# Labrador.net
KiCad netlist of a schematic drawn in Altium Designer
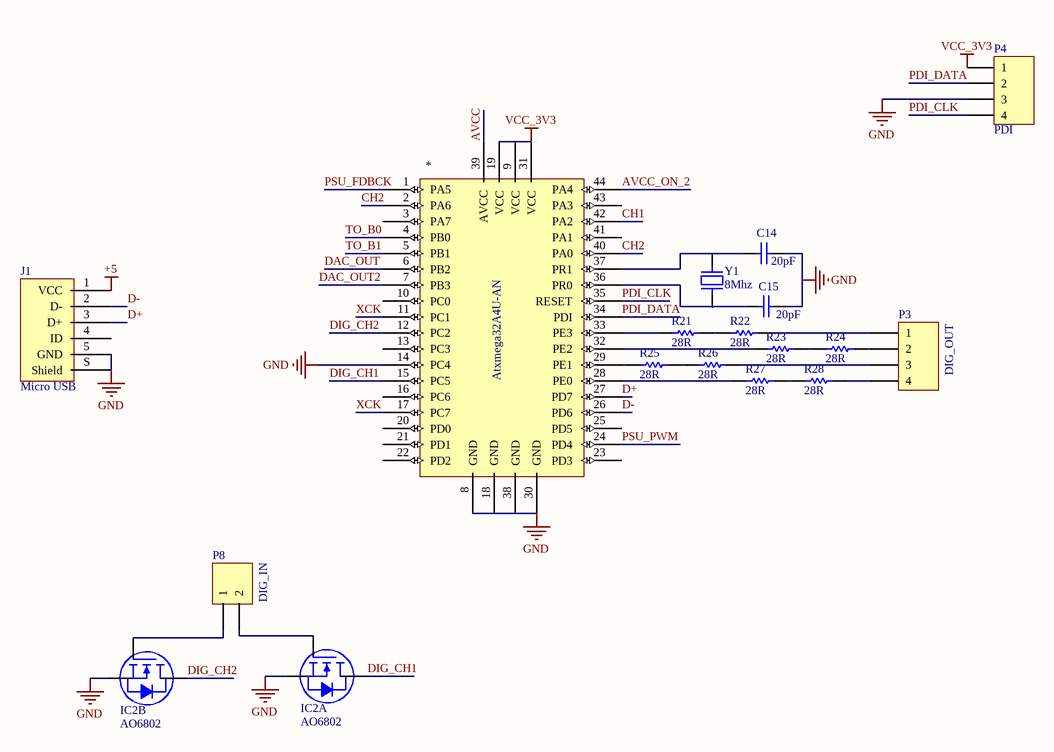
[diagram p0: Labrador.SchDoc]

(export (version "E")
  (design (tool "Eeschema 10.0.6"))
  (components
    (comp (ref "*")
      (value "Atxmega32A4U-AN")
      (footprint "QFP44P80_1200X1200X120L60X37N")
      (libsource (lib "labrador") (part "Atxmega32A4U-AN"))
    )
    (comp (ref "C14")
      (value "20pF")
      (footprint "CAPC200X125X75L45N")
      (description "CAP CER 20PF 50V NP0 0805")
      (fields
        (field (name "MANUFACTURER") "Samsung Electro-Mechanics America, Inc.")
        (field (name "MANUFACTURER PART NUMBER") "CL21C180JBANNNC")
      )
      (libsource (lib "labrador") (part "CL21C180JBANNNC"))
    )
    (comp (ref "C15")
      (value "20pF")
      (footprint "CAPC200X125X75L45N")
      (description "CAP CER 20PF 50V NP0 0805")
      (fields
        (field (name "MANUFACTURER") "Samsung Electro-Mechanics America, Inc.")
        (field (name "MANUFACTURER PART NUMBER") "CL21C180JBANNNC")
      )
      (libsource (lib "labrador") (part "CL21C180JBANNNC"))
    )
    (comp (ref "IC2")
      (value "AO6802")
      (footprint "ALPHAOMEGA TSOP-6")
      (description "MOSFET 2N-CH 30V 3.5A 6-TSOP")
      (fields (field (name "MANUFACTURER") "Alpha & Omega"))
      (libsource (lib "labrador") (part "ALPHAOMEGA TSOP-6"))
    )
    (comp (ref "J1")
      (value "Micro USB")
      (footprint "FCI USB 10118193-0001LF")
      (description "CONN USB MICRO B RECPT SMT R/A")
      (fields (field (name "PART NUMBER") "10118193-0001LF") (field (name "MANUFACTURER") "FCI"))
      (libsource (lib "labrador") (part "USB 2.0 Type B Micro"))
    )
    (comp (ref "P3")
      (value "DIG_OUT")
      (footprint "HDR1X4")
      (description "Header, 4-Pin")
      (fields (field (name "PUBLISHER") "Altium Limited"))
      (libsource (lib "labrador") (part "Header 4"))
    )
    (comp (ref "P4")
      (value "PDI")
      (footprint "HDR1X4")
      (description "Header, 4-Pin")
      (fields (field (name "PUBLISHER") "Altium Limited"))
      (libsource (lib "labrador") (part "Header 4"))
    )
    (comp (ref "P8")
      (value "DIG_IN")
      (footprint "HDR1X2")
      (description "Header, 2-Pin")
      (fields (field (name "PUBLISHER") "Altium Limited"))
      (libsource (lib "labrador") (part "Header 2"))
    )
    (comp (ref "R21")
      (value "28R")
      (footprint "RESC160X80X55L25N")
      (description "RES SMD 28 OHM 1% 1/10W 0603")
      (fields
        (field (name "MANUFACTURER") "Yageo")
        (field (name "MANUFACTURER PART NUMBER") "RC0603FR-0728RL")
      )
      (libsource (lib "labrador") (part "RC0603FR-0728RL"))
    )
    (comp (ref "R22")
      (value "28R")
      (footprint "RESC160X80X55L25N")
      (description "RES SMD 28 OHM 1% 1/10W 0603")
      (fields
        (field (name "MANUFACTURER") "Yageo")
        (field (name "MANUFACTURER PART NUMBER") "RC0603FR-0728RL")
      )
      (libsource (lib "labrador") (part "RC0603FR-0728RL"))
    )
    (comp (ref "R23")
      (value "28R")
      (footprint "RESC160X80X55L25N")
      (description "RES SMD 28 OHM 1% 1/10W 0603")
      (fields
        (field (name "MANUFACTURER") "Yageo")
        (field (name "MANUFACTURER PART NUMBER") "RC0603FR-0728RL")
      )
      (libsource (lib "labrador") (part "RC0603FR-0728RL"))
    )
    (comp (ref "R24")
      (value "28R")
      (footprint "RESC160X80X55L25N")
      (description "RES SMD 28 OHM 1% 1/10W 0603")
      (fields
        (field (name "MANUFACTURER") "Yageo")
        (field (name "MANUFACTURER PART NUMBER") "RC0603FR-0728RL")
      )
      (libsource (lib "labrador") (part "RC0603FR-0728RL"))
    )
    (comp (ref "R25")
      (value "28R")
      (footprint "RESC160X80X55L25N")
      (description "RES SMD 28 OHM 1% 1/10W 0603")
      (fields
        (field (name "MANUFACTURER") "Yageo")
        (field (name "MANUFACTURER PART NUMBER") "RC0603FR-0728RL")
      )
      (libsource (lib "labrador") (part "RC0603FR-0728RL"))
    )
    (comp (ref "R26")
      (value "28R")
      (footprint "RESC160X80X55L25N")
      (description "RES SMD 28 OHM 1% 1/10W 0603")
      (fields
        (field (name "MANUFACTURER") "Yageo")
        (field (name "MANUFACTURER PART NUMBER") "RC0603FR-0728RL")
      )
      (libsource (lib "labrador") (part "RC0603FR-0728RL"))
    )
    (comp (ref "R27")
      (value "28R")
      (footprint "RESC160X80X55L25N")
      (description "RES SMD 28 OHM 1% 1/10W 0603")
      (fields
        (field (name "MANUFACTURER") "Yageo")
        (field (name "MANUFACTURER PART NUMBER") "RC0603FR-0728RL")
      )
      (libsource (lib "labrador") (part "RC0603FR-0728RL"))
    )
    (comp (ref "R28")
      (value "28R")
      (footprint "RESC160X80X55L25N")
      (description "RES SMD 28 OHM 1% 1/10W 0603")
      (fields
        (field (name "MANUFACTURER") "Yageo")
        (field (name "MANUFACTURER PART NUMBER") "RC0603FR-0728RL")
      )
      (libsource (lib "labrador") (part "RC0603FR-0728RL"))
    )
    (comp (ref "Y1")
      (value "8Mhz")
      (footprint "TXC 9C")
      (description "Crystals 8MHz 20pF")
      (fields (field (name "MANUFACTURER") "CTS") (field (name "MANUFACTURER PART NUMBER") "ATS08ASM-1"))
      (libsource (lib "labrador") (part "ATS08ASM-1"))
    )
  )
  (nets
    (net (code "1") (name "+5") (class "Default")
      (node (ref "J1") (pin "1") (pinfunction "VCC_1") (pintype "passive"))
    )
    (net (code "2") (name "/AVCC") (class "Default")
      (node (ref "*") (pin "39") (pinfunction "AVCC_39") (pintype "power_in"))
    )
    (net (code "3") (name "/AVCC_ON_2") (class "Default")
      (node (ref "*") (pin "44") (pinfunction "PA4_44") (pintype "bidirectional"))
    )
    (net (code "4") (name "/CH1") (class "Default")
      (node (ref "*") (pin "42") (pinfunction "PA2_42") (pintype "bidirectional"))
    )
    (net (code "5") (name "/CH2") (class "Default")
      (node (ref "*") (pin "2") (pinfunction "PA6_2") (pintype "bidirectional"))
      (node (ref "*") (pin "40") (pinfunction "PA0_40") (pintype "bidirectional"))
    )
    (net (code "6") (name "/D+") (class "Default")
      (node (ref "*") (pin "27") (pinfunction "PD7_27") (pintype "bidirectional"))
      (node (ref "J1") (pin "3") (pinfunction "D+_3") (pintype "passive"))
    )
    (net (code "7") (name "/D-") (class "Default")
      (node (ref "*") (pin "26") (pinfunction "PD6_26") (pintype "bidirectional"))
      (node (ref "J1") (pin "2") (pinfunction "D-_2") (pintype "passive"))
    )
    (net (code "8") (name "/DAC_OUT") (class "Default")
      (node (ref "*") (pin "6") (pinfunction "PB2_6") (pintype "bidirectional"))
    )
    (net (code "9") (name "/DAC_OUT2") (class "Default")
      (node (ref "*") (pin "7") (pinfunction "PB3_7") (pintype "bidirectional"))
    )
    (net (code "10") (name "/DIG_CH1") (class "Default")
      (node (ref "*") (pin "15") (pinfunction "PC5_15") (pintype "bidirectional"))
      (node (ref "IC2") (pin "6") (pinfunction "D1_6") (pintype "passive"))
    )
    (net (code "11") (name "/DIG_CH2") (class "Default")
      (node (ref "*") (pin "12") (pinfunction "PC2_12") (pintype "bidirectional"))
      (node (ref "IC2") (pin "4") (pinfunction "D2_4") (pintype "passive"))
    )
    (net (code "12") (name "/PDI_CLK") (class "Default")
      (node (ref "*") (pin "35") (pinfunction "RESET_35") (pintype "bidirectional"))
      (node (ref "P4") (pin "4") (pinfunction "4_4") (pintype "passive"))
    )
    (net (code "13") (name "/PDI_DATA") (class "Default")
      (node (ref "*") (pin "34") (pinfunction "PDI_34") (pintype "bidirectional"))
      (node (ref "P4") (pin "2") (pinfunction "2_2") (pintype "passive"))
    )
    (net (code "14") (name "/PSU_FDBCK") (class "Default")
      (node (ref "*") (pin "1") (pinfunction "PA5_1") (pintype "bidirectional"))
    )
    (net (code "15") (name "/PSU_PWM") (class "Default")
      (node (ref "*") (pin "24") (pinfunction "PD4_24") (pintype "bidirectional"))
    )
    (net (code "16") (name "/TO_B0") (class "Default")
      (node (ref "*") (pin "4") (pinfunction "PB0_4") (pintype "bidirectional"))
    )
    (net (code "17") (name "/TO_B1") (class "Default")
      (node (ref "*") (pin "5") (pinfunction "PB1_5") (pintype "bidirectional"))
    )
    (net (code "18") (name "/XCK") (class "Default")
      (node (ref "*") (pin "11") (pinfunction "PC1_11") (pintype "bidirectional"))
      (node (ref "*") (pin "17") (pinfunction "PC7_17") (pintype "bidirectional"))
    )
    (net (code "19") (name "GND") (class "Default")
      (node (ref "*") (pin "14") (pinfunction "PC4_14") (pintype "bidirectional"))
      (node (ref "*") (pin "18") (pinfunction "GND_18") (pintype "power_in"))
      (node (ref "*") (pin "30") (pinfunction "GND_30") (pintype "power_in"))
      (node (ref "*") (pin "38") (pinfunction "GND_38") (pintype "power_in"))
      (node (ref "*") (pin "8") (pinfunction "GND_8") (pintype "power_in"))
      (node (ref "C14") (pin "2") (pinfunction "2_2") (pintype "passive"))
      (node (ref "C15") (pin "2") (pinfunction "2_2") (pintype "passive"))
      (node (ref "IC2") (pin "2") (pinfunction "S2_2") (pintype "passive"))
      (node (ref "IC2") (pin "5") (pinfunction "S1_5") (pintype "passive"))
      (node (ref "J1") (pin "5") (pinfunction "GND_5") (pintype "passive"))
      (node (ref "J1") (pin "S") (pinfunction "Shield_S") (pintype "passive"))
      (node (ref "P4") (pin "3") (pinfunction "3_3") (pintype "passive"))
    )
    (net (code "20") (name "Net-(*-PE0)") (class "Default")
      (node (ref "*") (pin "28") (pinfunction "PE0_28") (pintype "bidirectional"))
      (node (ref "R27") (pin "1") (pinfunction "1_1") (pintype "passive"))
    )
    (net (code "21") (name "Net-(*-PE1)") (class "Default")
      (node (ref "*") (pin "29") (pinfunction "PE1_29") (pintype "bidirectional"))
      (node (ref "R25") (pin "1") (pinfunction "1_1") (pintype "passive"))
    )
    (net (code "22") (name "Net-(*-PE2)") (class "Default")
      (node (ref "*") (pin "32") (pinfunction "PE2_32") (pintype "bidirectional"))
      (node (ref "R23") (pin "1") (pinfunction "1_1") (pintype "passive"))
    )
    (net (code "23") (name "Net-(*-PE3)") (class "Default")
      (node (ref "*") (pin "33") (pinfunction "PE3_33") (pintype "bidirectional"))
      (node (ref "R21") (pin "1") (pinfunction "1_1") (pintype "passive"))
    )
    (net (code "24") (name "Net-(*-PR0)") (class "Default")
      (node (ref "*") (pin "36") (pinfunction "PR0_36") (pintype "bidirectional"))
      (node (ref "C15") (pin "1") (pinfunction "1_1") (pintype "passive"))
      (node (ref "Y1") (pin "1") (pinfunction "1_1") (pintype "passive"))
    )
    (net (code "25") (name "Net-(*-PR1)") (class "Default")
      (node (ref "*") (pin "37") (pinfunction "PR1_37") (pintype "bidirectional"))
      (node (ref "C14") (pin "1") (pinfunction "1_1") (pintype "passive"))
      (node (ref "Y1") (pin "2") (pinfunction "2_2") (pintype "passive"))
    )
    (net (code "26") (name "Net-(IC2A-G1)") (class "Default")
      (node (ref "IC2") (pin "1") (pinfunction "G1_1") (pintype "passive"))
      (node (ref "P8") (pin "2") (pinfunction "2_2") (pintype "passive"))
    )
    (net (code "27") (name "Net-(IC2B-G2)") (class "Default")
      (node (ref "IC2") (pin "3") (pinfunction "G2_3") (pintype "passive"))
      (node (ref "P8") (pin "1") (pinfunction "1_1") (pintype "passive"))
    )
    (net (code "28") (name "Net-(P3-Pad1)") (class "Default")
      (node (ref "P3") (pin "1") (pinfunction "1_1") (pintype "passive"))
      (node (ref "R22") (pin "2") (pinfunction "2_2") (pintype "passive"))
    )
    (net (code "29") (name "Net-(P3-Pad2)") (class "Default")
      (node (ref "P3") (pin "2") (pinfunction "2_2") (pintype "passive"))
      (node (ref "R24") (pin "2") (pinfunction "2_2") (pintype "passive"))
    )
    (net (code "30") (name "Net-(P3-Pad3)") (class "Default")
      (node (ref "P3") (pin "3") (pinfunction "3_3") (pintype "passive"))
      (node (ref "R26") (pin "2") (pinfunction "2_2") (pintype "passive"))
    )
    (net (code "31") (name "Net-(P3-Pad4)") (class "Default")
      (node (ref "P3") (pin "4") (pinfunction "4_4") (pintype "passive"))
      (node (ref "R28") (pin "2") (pinfunction "2_2") (pintype "passive"))
    )
    (net (code "32") (name "Net-(R21-Pad2)") (class "Default")
      (node (ref "R21") (pin "2") (pinfunction "2_2") (pintype "passive"))
      (node (ref "R22") (pin "1") (pinfunction "1_1") (pintype "passive"))
    )
    (net (code "33") (name "Net-(R23-Pad2)") (class "Default")
      (node (ref "R23") (pin "2") (pinfunction "2_2") (pintype "passive"))
      (node (ref "R24") (pin "1") (pinfunction "1_1") (pintype "passive"))
    )
    (net (code "34") (name "Net-(R25-Pad2)") (class "Default")
      (node (ref "R25") (pin "2") (pinfunction "2_2") (pintype "passive"))
      (node (ref "R26") (pin "1") (pinfunction "1_1") (pintype "passive"))
    )
    (net (code "35") (name "Net-(R27-Pad2)") (class "Default")
      (node (ref "R27") (pin "2") (pinfunction "2_2") (pintype "passive"))
      (node (ref "R28") (pin "1") (pinfunction "1_1") (pintype "passive"))
    )
    (net (code "36") (name "VCC_3V3") (class "Default")
      (node (ref "*") (pin "19") (pinfunction "VCC_19") (pintype "power_in"))
      (node (ref "*") (pin "31") (pinfunction "VCC_31") (pintype "power_in"))
      (node (ref "*") (pin "9") (pinfunction "VCC_9") (pintype "power_in"))
      (node (ref "P4") (pin "1") (pinfunction "1_1") (pintype "passive"))
    )
    (net (code "37") (name "unconnected-(*-PA1-Pad41)") (class "Default")
      (node (ref "*") (pin "41") (pinfunction "PA1_41") (pintype "bidirectional"))
    )
    (net (code "38") (name "unconnected-(*-PA3-Pad43)") (class "Default")
      (node (ref "*") (pin "43") (pinfunction "PA3_43") (pintype "bidirectional"))
    )
    (net (code "39") (name "unconnected-(*-PA7-Pad3)") (class "Default")
      (node (ref "*") (pin "3") (pinfunction "PA7_3") (pintype "bidirectional"))
    )
    (net (code "40") (name "unconnected-(*-PC0-Pad10)") (class "Default")
      (node (ref "*") (pin "10") (pinfunction "PC0_10") (pintype "bidirectional"))
    )
    (net (code "41") (name "unconnected-(*-PC3-Pad13)") (class "Default")
      (node (ref "*") (pin "13") (pinfunction "PC3_13") (pintype "bidirectional"))
    )
    (net (code "42") (name "unconnected-(*-PC6-Pad16)") (class "Default")
      (node (ref "*") (pin "16") (pinfunction "PC6_16") (pintype "bidirectional"))
    )
    (net (code "43") (name "unconnected-(*-PD0-Pad20)") (class "Default")
      (node (ref "*") (pin "20") (pinfunction "PD0_20") (pintype "bidirectional"))
    )
    (net (code "44") (name "unconnected-(*-PD1-Pad21)") (class "Default")
      (node (ref "*") (pin "21") (pinfunction "PD1_21") (pintype "bidirectional"))
    )
    (net (code "45") (name "unconnected-(*-PD2-Pad22)") (class "Default")
      (node (ref "*") (pin "22") (pinfunction "PD2_22") (pintype "bidirectional"))
    )
    (net (code "46") (name "unconnected-(*-PD3-Pad23)") (class "Default")
      (node (ref "*") (pin "23") (pinfunction "PD3_23") (pintype "bidirectional"))
    )
    (net (code "47") (name "unconnected-(*-PD5-Pad25)") (class "Default")
      (node (ref "*") (pin "25") (pinfunction "PD5_25") (pintype "bidirectional"))
    )
    (net (code "48") (name "unconnected-(J1-ID-Pad4)") (class "Default")
      (node (ref "J1") (pin "4") (pinfunction "ID_4") (pintype "passive"))
    )
  )
)
